# OpenBook_v29.net
KiCad netlist of a schematic drawn in EAGLE
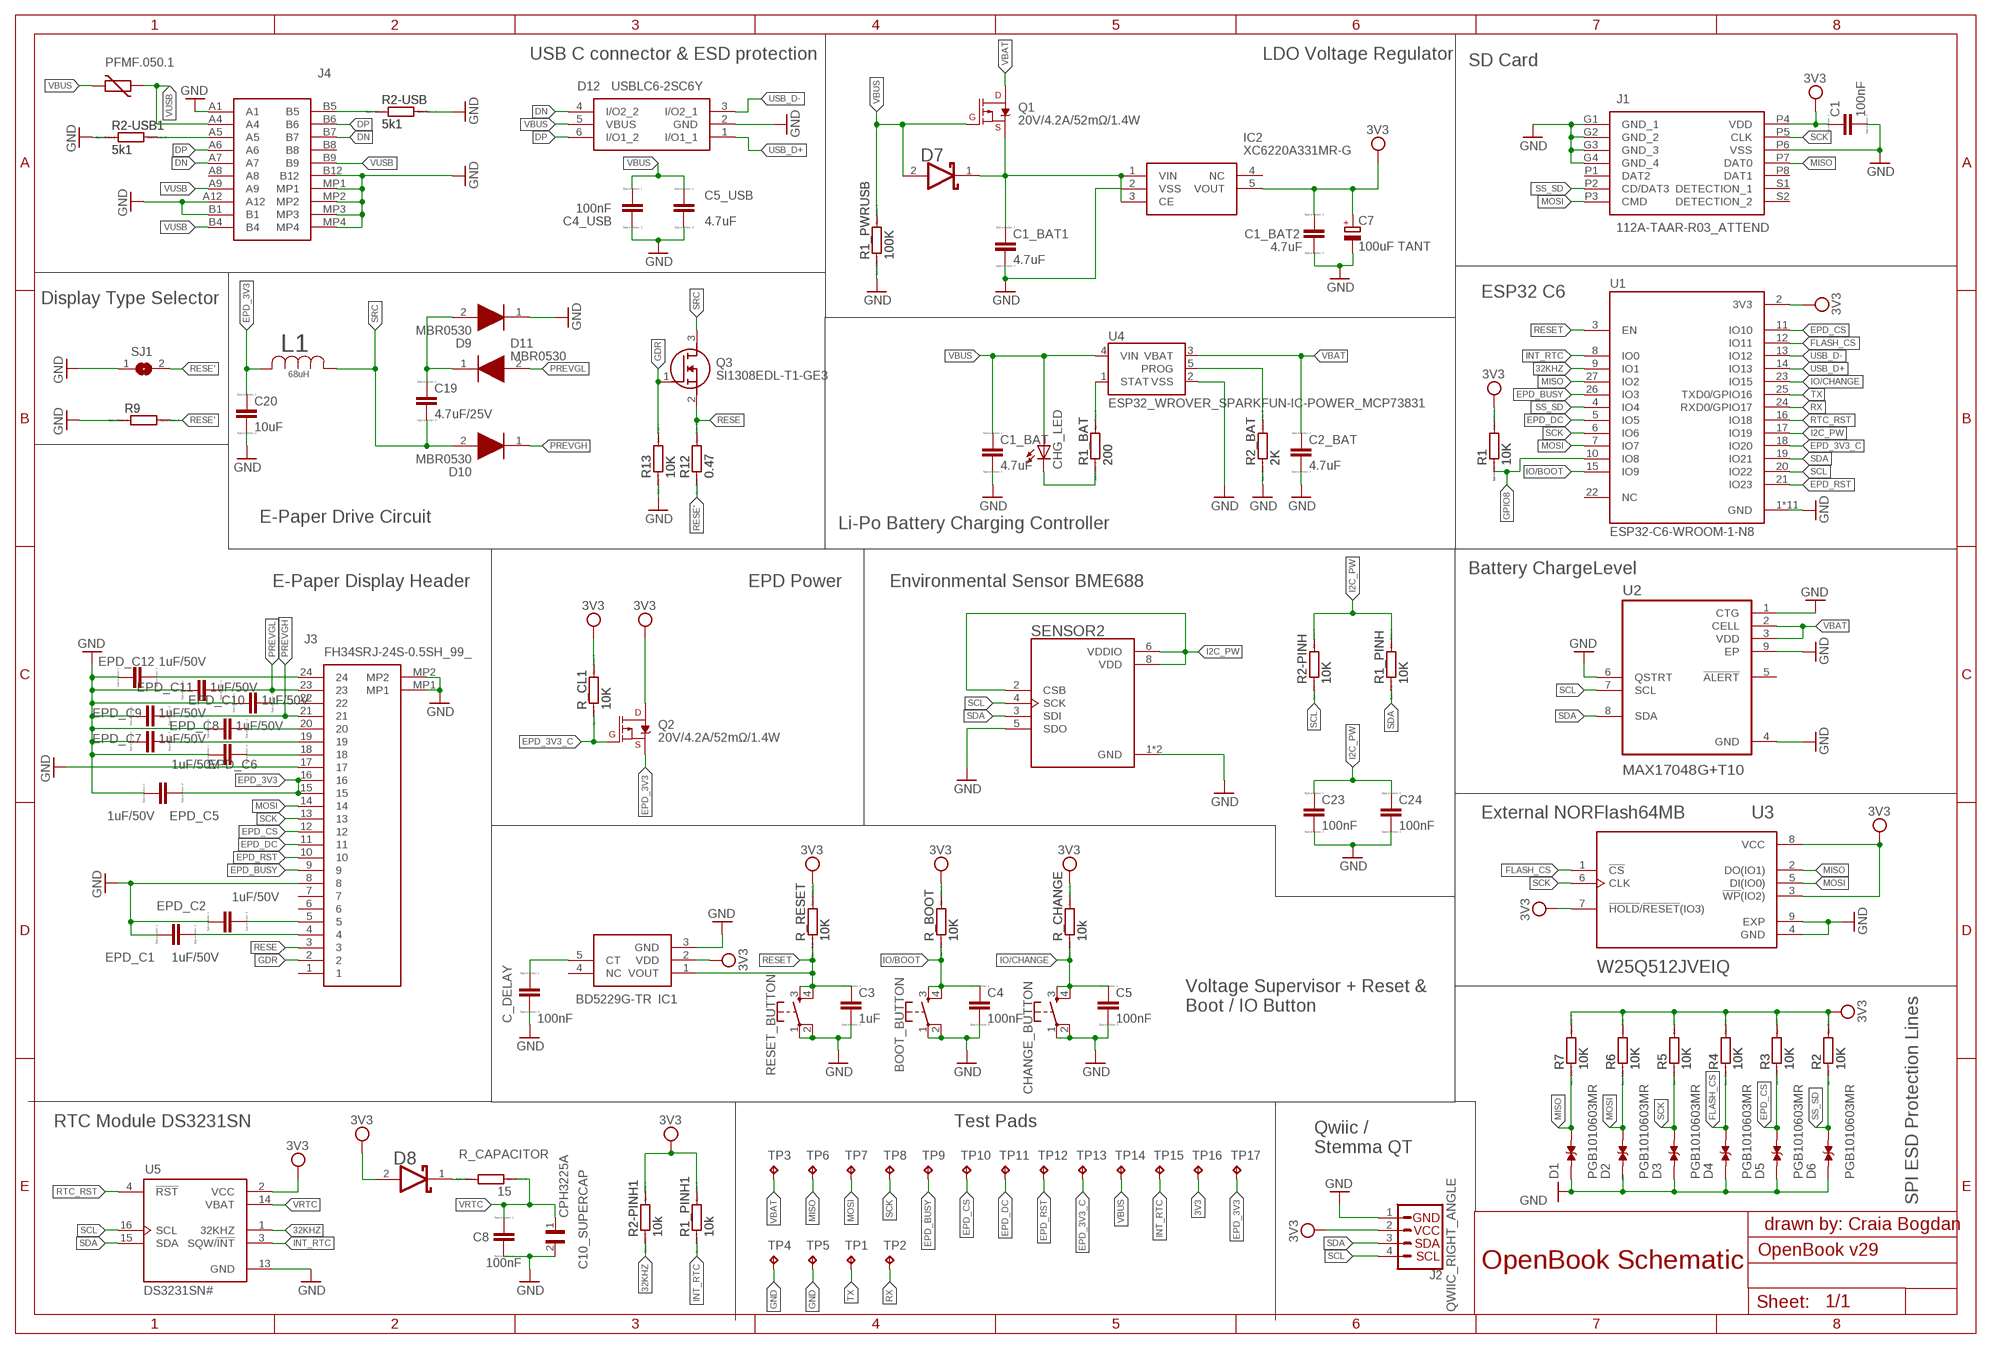
[diagram p0: schematic, sheet 1]

(export (version "E")
  (design (tool "Eeschema 10.0.6"))
  (components
    (comp (ref "BOOT_BUTTON")
      (value "BUTTON_CUSYOMV1")
      (footprint "eagle-import:MYBUTTON")
      (libsource (lib "eagle-import") (part "BUTTON_CUSYOMV1"))
    )
    (comp (ref "C1")
      (value "100nF")
      (footprint "eagle-import:EAGLE-LTSPICE_C0402")
      (libsource (lib "eagle-import") (part "EAGLE-LTSPICE_CC0402"))
    )
    (comp (ref "C1_BAT")
      (value "4.7uF")
      (footprint "eagle-import:EAGLE-LTSPICE_C0402")
      (libsource (lib "eagle-import") (part "EAGLE-LTSPICE_CC0402"))
    )
    (comp (ref "C1_BAT1")
      (value "4.7uF")
      (footprint "eagle-import:EAGLE-LTSPICE_C0402")
      (libsource (lib "eagle-import") (part "EAGLE-LTSPICE_CC0402"))
    )
    (comp (ref "C1_BAT2")
      (value "4.7uF")
      (footprint "eagle-import:EAGLE-LTSPICE_C0402")
      (libsource (lib "eagle-import") (part "EAGLE-LTSPICE_CC0402"))
    )
    (comp (ref "C2_BAT")
      (value "4.7uF")
      (footprint "eagle-import:EAGLE-LTSPICE_C0402")
      (libsource (lib "eagle-import") (part "EAGLE-LTSPICE_CC0402"))
    )
    (comp (ref "C3")
      (value "1uF")
      (footprint "eagle-import:EAGLE-LTSPICE_C0402")
      (libsource (lib "eagle-import") (part "EAGLE-LTSPICE_CC0402"))
    )
    (comp (ref "C4")
      (value "100nF")
      (footprint "eagle-import:EAGLE-LTSPICE_C0402")
      (libsource (lib "eagle-import") (part "EAGLE-LTSPICE_CC0402"))
    )
    (comp (ref "C4_USB")
      (value "100nF")
      (footprint "eagle-import:EAGLE-LTSPICE_C0402")
      (libsource (lib "eagle-import") (part "EAGLE-LTSPICE_CC0402"))
    )
    (comp (ref "C5")
      (value "100nF")
      (footprint "eagle-import:EAGLE-LTSPICE_C0402")
      (libsource (lib "eagle-import") (part "EAGLE-LTSPICE_CC0402"))
    )
    (comp (ref "C5_USB")
      (value "4.7uF")
      (footprint "eagle-import:EAGLE-LTSPICE_C0402")
      (libsource (lib "eagle-import") (part "EAGLE-LTSPICE_CC0402"))
    )
    (comp (ref "C7")
      (value "100uF TANT")
      (footprint "eagle-import:RCL_CT3528")
      (libsource (lib "eagle-import") (part "RCL_CPOL-EUCT3528"))
    )
    (comp (ref "C8")
      (value "100nF")
      (footprint "eagle-import:EAGLE-LTSPICE_C0402")
      (libsource (lib "eagle-import") (part "EAGLE-LTSPICE_CC0402"))
    )
    (comp (ref "C10_SUPERCAP")
      (value "CPH3225A")
      (footprint "eagle-import:CAPCP3225X100N")
      (fields (field (name "MF") "Seiko Instruments"))
      (libsource (lib "eagle-import") (part "CPH3225A"))
    )
    (comp (ref "C19")
      (value "4.7uF/25V")
      (footprint "eagle-import:EAGLE-LTSPICE_C0402")
      (libsource (lib "eagle-import") (part "EAGLE-LTSPICE_CC0402"))
    )
    (comp (ref "C20")
      (value "10uF")
      (footprint "eagle-import:EAGLE-LTSPICE_C0402")
      (libsource (lib "eagle-import") (part "EAGLE-LTSPICE_CC0402"))
    )
    (comp (ref "C23")
      (value "100nF")
      (footprint "eagle-import:EAGLE-LTSPICE_C0402")
      (libsource (lib "eagle-import") (part "EAGLE-LTSPICE_CC0402"))
    )
    (comp (ref "C24")
      (value "100nF")
      (footprint "eagle-import:EAGLE-LTSPICE_C0402")
      (libsource (lib "eagle-import") (part "EAGLE-LTSPICE_CC0402"))
    )
    (comp (ref "CHANGE_BUTTON")
      (value "BUTTON_CUSYOMV1")
      (footprint "eagle-import:MYBUTTON")
      (libsource (lib "eagle-import") (part "BUTTON_CUSYOMV1"))
    )
    (comp (ref "CHG_LED")
      (value "ADAFRUIT_LEDCHIP-LED0603")
      (footprint "eagle-import:ADAFRUIT_CHIP-LED0603")
      (libsource (lib "eagle-import") (part "ADAFRUIT_LEDCHIP-LED0603"))
    )
    (comp (ref "C_DELAY")
      (value "100nF")
      (footprint "eagle-import:EAGLE-LTSPICE_C0402")
      (libsource (lib "eagle-import") (part "EAGLE-LTSPICE_CC0402"))
    )
    (comp (ref "D1")
      (value "PGB1010603MR")
      (footprint "eagle-import:DIOC1608X36N")
      (fields (field (name "MF") "Littelfuse Inc."))
      (libsource (lib "eagle-import") (part "PGB1010603MR"))
    )
    (comp (ref "D2")
      (value "PGB1010603MR")
      (footprint "eagle-import:DIOC1608X36N")
      (fields (field (name "MF") "Littelfuse Inc."))
      (libsource (lib "eagle-import") (part "PGB1010603MR"))
    )
    (comp (ref "D3")
      (value "PGB1010603MR")
      (footprint "eagle-import:DIOC1608X36N")
      (fields (field (name "MF") "Littelfuse Inc."))
      (libsource (lib "eagle-import") (part "PGB1010603MR"))
    )
    (comp (ref "D4")
      (value "PGB1010603MR")
      (footprint "eagle-import:DIOC1608X36N")
      (fields (field (name "MF") "Littelfuse Inc."))
      (libsource (lib "eagle-import") (part "PGB1010603MR"))
    )
    (comp (ref "D5")
      (value "PGB1010603MR")
      (footprint "eagle-import:DIOC1608X36N")
      (fields (field (name "MF") "Littelfuse Inc."))
      (libsource (lib "eagle-import") (part "PGB1010603MR"))
    )
    (comp (ref "D6")
      (value "PGB1010603MR")
      (footprint "eagle-import:DIOC1608X36N")
      (fields (field (name "MF") "Littelfuse Inc."))
      (libsource (lib "eagle-import") (part "PGB1010603MR"))
    )
    (comp (ref "D7")
      (value "ESP32_WROVER_AVX---SD0805S020S1R0_AVX_SD0805S020S1R0_0_0AVX_SD0805S020S1R0_0_0")
      (footprint "eagle-import:ESP32_WROVER_AVX---SD0805S020S1R0_AVX_SD0805S020S1R0_0")
      (fields
        (field (name "DIGIKEY_PART_NUMBER") "478-7800-1-ND")
        (field (name "MF") "AVX")
        (field (name "MOUSER_PART_NUMBER") "581-SD0805S020S1R0")
      )
      (libsource (lib "eagle-import") (part "ESP32_WROVER_AVX---SD0805S020S1R0_AVX_SD0805S020S1R0_0_0AVX_SD0805S020S1R0_0_0"))
    )
    (comp (ref "D8")
      (value "ESP32_WROVER_AVX---SD0805S020S1R0_AVX_SD0805S020S1R0_0_0AVX_SD0805S020S1R0_0_0")
      (footprint "eagle-import:ESP32_WROVER_AVX---SD0805S020S1R0_AVX_SD0805S020S1R0_0")
      (fields
        (field (name "DIGIKEY_PART_NUMBER") "478-7800-1-ND")
        (field (name "MF") "AVX")
        (field (name "MOUSER_PART_NUMBER") "581-SD0805S020S1R0")
      )
      (libsource (lib "eagle-import") (part "ESP32_WROVER_AVX---SD0805S020S1R0_AVX_SD0805S020S1R0_0_0AVX_SD0805S020S1R0_0_0"))
    )
    (comp (ref "D9")
      (value "MBR0530")
      (footprint "eagle-import:SOD3716X135N")
      (fields (field (name "MF") "ON Semiconductor"))
      (libsource (lib "eagle-import") (part "MBR0530"))
    )
    (comp (ref "D10")
      (value "MBR0530")
      (footprint "eagle-import:SOD3716X135N")
      (fields (field (name "MF") "ON Semiconductor"))
      (libsource (lib "eagle-import") (part "MBR0530"))
    )
    (comp (ref "D11")
      (value "MBR0530")
      (footprint "eagle-import:SOD3716X135N")
      (fields (field (name "MF") "ON Semiconductor"))
      (libsource (lib "eagle-import") (part "MBR0530"))
    )
    (comp (ref "D12")
      (value "USBLC6-2SC6Y")
      (footprint "eagle-import:SOT95P280X145-6N")
      (fields (field (name "MF") "STMicroelectronics"))
      (libsource (lib "eagle-import") (part "USBLC6-2SC6Y"))
    )
    (comp (ref "EPD_C1")
      (value "1uF/50V")
      (footprint "eagle-import:EAGLE-LTSPICE_C0402")
      (libsource (lib "eagle-import") (part "EAGLE-LTSPICE_CC0402"))
    )
    (comp (ref "EPD_C2")
      (value "1uF/50V")
      (footprint "eagle-import:EAGLE-LTSPICE_C0402")
      (libsource (lib "eagle-import") (part "EAGLE-LTSPICE_CC0402"))
    )
    (comp (ref "EPD_C5")
      (value "1uF/50V")
      (footprint "eagle-import:EAGLE-LTSPICE_C0402")
      (libsource (lib "eagle-import") (part "EAGLE-LTSPICE_CC0402"))
    )
    (comp (ref "EPD_C6")
      (value "1uF/50V")
      (footprint "eagle-import:EAGLE-LTSPICE_C0402")
      (libsource (lib "eagle-import") (part "EAGLE-LTSPICE_CC0402"))
    )
    (comp (ref "EPD_C7")
      (value "1uF/50V")
      (footprint "eagle-import:EAGLE-LTSPICE_C0402")
      (libsource (lib "eagle-import") (part "EAGLE-LTSPICE_CC0402"))
    )
    (comp (ref "EPD_C8")
      (value "1uF/50V")
      (footprint "eagle-import:EAGLE-LTSPICE_C0402")
      (libsource (lib "eagle-import") (part "EAGLE-LTSPICE_CC0402"))
    )
    (comp (ref "EPD_C9")
      (value "1uF/50V")
      (footprint "eagle-import:EAGLE-LTSPICE_C0402")
      (libsource (lib "eagle-import") (part "EAGLE-LTSPICE_CC0402"))
    )
    (comp (ref "EPD_C10")
      (value "1uF/50V")
      (footprint "eagle-import:EAGLE-LTSPICE_C0402")
      (libsource (lib "eagle-import") (part "EAGLE-LTSPICE_CC0402"))
    )
    (comp (ref "EPD_C11")
      (value "1uF/50V")
      (footprint "eagle-import:EAGLE-LTSPICE_C0402")
      (libsource (lib "eagle-import") (part "EAGLE-LTSPICE_CC0402"))
    )
    (comp (ref "EPD_C12")
      (value "1uF/50V")
      (footprint "eagle-import:EAGLE-LTSPICE_C0402")
      (libsource (lib "eagle-import") (part "EAGLE-LTSPICE_CC0402"))
    )
    (comp (ref "IC1")
      (value "BD5229G-TR")
      (footprint "eagle-import:SOT95P280X125-5N")
      (fields (field (name "MOUSER_PART_NUMBER") "755-BD5229G-TR"))
      (libsource (lib "eagle-import") (part "BD5229G-TR"))
    )
    (comp (ref "IC2")
      (value "XC6220A331MR-G")
      (footprint "eagle-import:SOT95P280X120-5N")
      (fields (field (name "MOUSER_PART_NUMBER") "865-XC6220A331MR-G"))
      (libsource (lib "eagle-import") (part "XC6220A331MR-G"))
    )
    (comp (ref "J1")
      (value "112A-TAAR-R03_ATTEND")
      (footprint "eagle-import:112ATAARR03ATTEND")
      (fields (field (name "MANUFACTURER_PART_NUMBER") "112A-TAAR-R03 ATTEND"))
      (libsource (lib "eagle-import") (part "112A-TAAR-R03_ATTEND"))
    )
    (comp (ref "J2")
      (value "QWIIC_RIGHT_ANGLE")
      (footprint "eagle-import:JST04_1MM_RA")
      (libsource (lib "eagle-import") (part "QWIIC_CONNECTORJS-1MM"))
    )
    (comp (ref "J3")
      (value "FH34SRJ-24S-0.5SH_99_")
      (footprint "eagle-import:FH34SRJ24S05SH99")
      (fields
        (field (name "MANUFACTURER_PART_NUMBER") "FH34SRJ-24S-0.5SH(99)")
        (field (name "MOUSER_PART_NUMBER") "798-FH34SRJ24S05SH99")
      )
      (libsource (lib "eagle-import") (part "FH34SRJ-24S-0.5SH_99_"))
    )
    (comp (ref "J4")
      (value "SAMACSYS_PARTS_USB4110-GF-A")
      (footprint "eagle-import:SAMACSYS_PARTS_USB4110GFA")
      (fields
        (field (name "MANUFACTURER_PART_NUMBER") "USB4110-GF-A")
        (field (name "MOUSER_PART_NUMBER") "640-USB4110-GF-A")
      )
      (libsource (lib "eagle-import") (part "SAMACSYS_PARTS_USB4110-GF-A"))
    )
    (comp (ref "L1")
      (value "68uH")
      (footprint "eagle-import:IND_4828-WE-TPC_WRE")
      (fields
        (field (name "MANUFACTURER_PART_NUMBER") "744043680")
        (field (name "COPYRIGHT") "Copyright (C) 2024 Ultra Librarian. All rights reserved.")
      )
      (libsource (lib "eagle-import") (part "744043680IND_4828-WE-TPC_WRE"))
    )
    (comp (ref "PFMF.050.1")
      (value "ESP32C6_VARISTORCN1812")
      (footprint "eagle-import:ESP32C6_VARISTOR_CT_CN1812")
      (libsource (lib "eagle-import") (part "ESP32C6_VARISTORCN1812"))
    )
    (comp (ref "Q1")
      (value "20V/4.2A/52mΩ/1.4W")
      (footprint "eagle-import:ESP32_WROVER_SPARKFUN-DISCRETESEMI_SOT23-3")
      (libsource (lib "eagle-import") (part "ESP32_WROVER_SPARKFUN-DISCRETESEMI_MOSFET_PCH-DMG2305UX-7"))
    )
    (comp (ref "Q2")
      (value "20V/4.2A/52mΩ/1.4W")
      (footprint "eagle-import:ESP32_WROVER_SPARKFUN-DISCRETESEMI_SOT23-3")
      (libsource (lib "eagle-import") (part "ESP32_WROVER_SPARKFUN-DISCRETESEMI_MOSFET_PCH-DMG2305UX-7"))
    )
    (comp (ref "Q3")
      (value "SI1308EDL-T1-GE3")
      (footprint "eagle-import:SOT65P210X110-3N")
      (fields (field (name "MF") "Vishay Siliconix"))
      (libsource (lib "eagle-import") (part "SI1308EDL-T1-GE3"))
    )
    (comp (ref "R1")
      (value "10K")
      (footprint "eagle-import:ESP32_WROVER_EAGLE-LTSPICE_R0402")
      (libsource (lib "eagle-import") (part "ESP32_WROVER_EAGLE-LTSPICE_RR0402"))
    )
    (comp (ref "R1_BAT")
      (value "200")
      (footprint "eagle-import:ESP32_WROVER_EAGLE-LTSPICE_R0402")
      (libsource (lib "eagle-import") (part "ESP32_WROVER_EAGLE-LTSPICE_RR0402"))
    )
    (comp (ref "R1_PINH")
      (value "10K")
      (footprint "eagle-import:ESP32_WROVER_EAGLE-LTSPICE_R0402")
      (libsource (lib "eagle-import") (part "ESP32_WROVER_EAGLE-LTSPICE_RR0402"))
    )
    (comp (ref "R1_PINH1")
      (value "10k")
      (footprint "eagle-import:ESP32_WROVER_EAGLE-LTSPICE_R0402")
      (libsource (lib "eagle-import") (part "ESP32_WROVER_EAGLE-LTSPICE_RR0402"))
    )
    (comp (ref "R1_PWRUSB")
      (value "100K")
      (footprint "eagle-import:ESP32_WROVER_EAGLE-LTSPICE_R0402")
      (libsource (lib "eagle-import") (part "ESP32_WROVER_EAGLE-LTSPICE_RR0402"))
    )
    (comp (ref "R2")
      (value "10K")
      (footprint "eagle-import:ESP32_WROVER_EAGLE-LTSPICE_R0402")
      (libsource (lib "eagle-import") (part "ESP32_WROVER_EAGLE-LTSPICE_RR0402"))
    )
    (comp (ref "R2-PINH")
      (value "10K")
      (footprint "eagle-import:ESP32_WROVER_EAGLE-LTSPICE_R0402")
      (libsource (lib "eagle-import") (part "ESP32_WROVER_EAGLE-LTSPICE_RR0402"))
    )
    (comp (ref "R2-PINH1")
      (value "10k")
      (footprint "eagle-import:ESP32_WROVER_EAGLE-LTSPICE_R0402")
      (libsource (lib "eagle-import") (part "ESP32_WROVER_EAGLE-LTSPICE_RR0402"))
    )
    (comp (ref "R2-USB")
      (value "5k1")
      (footprint "eagle-import:ESP32_WROVER_EAGLE-LTSPICE_R0402")
      (libsource (lib "eagle-import") (part "ESP32_WROVER_EAGLE-LTSPICE_RR0402"))
    )
    (comp (ref "R2-USB1")
      (value "5k1")
      (footprint "eagle-import:ESP32_WROVER_EAGLE-LTSPICE_R0402")
      (libsource (lib "eagle-import") (part "ESP32_WROVER_EAGLE-LTSPICE_RR0402"))
    )
    (comp (ref "R2_BAT")
      (value "2K")
      (footprint "eagle-import:ESP32_WROVER_EAGLE-LTSPICE_R0402")
      (libsource (lib "eagle-import") (part "ESP32_WROVER_EAGLE-LTSPICE_RR0402"))
    )
    (comp (ref "R3")
      (value "10K")
      (footprint "eagle-import:ESP32_WROVER_EAGLE-LTSPICE_R0402")
      (libsource (lib "eagle-import") (part "ESP32_WROVER_EAGLE-LTSPICE_RR0402"))
    )
    (comp (ref "R4")
      (value "10K")
      (footprint "eagle-import:ESP32_WROVER_EAGLE-LTSPICE_R0402")
      (libsource (lib "eagle-import") (part "ESP32_WROVER_EAGLE-LTSPICE_RR0402"))
    )
    (comp (ref "R5")
      (value "10K")
      (footprint "eagle-import:ESP32_WROVER_EAGLE-LTSPICE_R0402")
      (libsource (lib "eagle-import") (part "ESP32_WROVER_EAGLE-LTSPICE_RR0402"))
    )
    (comp (ref "R6")
      (value "10K")
      (footprint "eagle-import:ESP32_WROVER_EAGLE-LTSPICE_R0402")
      (libsource (lib "eagle-import") (part "ESP32_WROVER_EAGLE-LTSPICE_RR0402"))
    )
    (comp (ref "R7")
      (value "10K")
      (footprint "eagle-import:ESP32_WROVER_EAGLE-LTSPICE_R0402")
      (libsource (lib "eagle-import") (part "ESP32_WROVER_EAGLE-LTSPICE_RR0402"))
    )
    (comp (ref "R9")
      (value "ESP32_WROVER_EAGLE-LTSPICE_RR0402")
      (footprint "eagle-import:ESP32_WROVER_EAGLE-LTSPICE_R0402")
      (libsource (lib "eagle-import") (part "ESP32_WROVER_EAGLE-LTSPICE_RR0402"))
    )
    (comp (ref "R12")
      (value "0.47")
      (footprint "eagle-import:ESP32_WROVER_EAGLE-LTSPICE_R0402")
      (libsource (lib "eagle-import") (part "ESP32_WROVER_EAGLE-LTSPICE_RR0402"))
    )
    (comp (ref "R13")
      (value "10K")
      (footprint "eagle-import:ESP32_WROVER_EAGLE-LTSPICE_R0402")
      (libsource (lib "eagle-import") (part "ESP32_WROVER_EAGLE-LTSPICE_RR0402"))
    )
    (comp (ref "RESET_BUTTON")
      (value "BUTTON_CUSYOMV1")
      (footprint "eagle-import:MYBUTTON")
      (libsource (lib "eagle-import") (part "BUTTON_CUSYOMV1"))
    )
    (comp (ref "R_BOOT")
      (value "10K")
      (footprint "eagle-import:ESP32_WROVER_EAGLE-LTSPICE_R0402")
      (libsource (lib "eagle-import") (part "ESP32_WROVER_EAGLE-LTSPICE_RR0402"))
    )
    (comp (ref "R_CAPACITOR")
      (value "15")
      (footprint "eagle-import:ESP32_WROVER_EAGLE-LTSPICE_R0402")
      (libsource (lib "eagle-import") (part "ESP32_WROVER_EAGLE-LTSPICE_RR0402"))
    )
    (comp (ref "R_CHANGE")
      (value "10k")
      (footprint "eagle-import:ESP32_WROVER_EAGLE-LTSPICE_R0402")
      (libsource (lib "eagle-import") (part "ESP32_WROVER_EAGLE-LTSPICE_RR0402"))
    )
    (comp (ref "R_CL1")
      (value "10K")
      (footprint "eagle-import:ESP32_WROVER_EAGLE-LTSPICE_R0402")
      (libsource (lib "eagle-import") (part "ESP32_WROVER_EAGLE-LTSPICE_RR0402"))
    )
    (comp (ref "R_RESET")
      (value "10K")
      (footprint "eagle-import:ESP32_WROVER_EAGLE-LTSPICE_R0402")
      (libsource (lib "eagle-import") (part "ESP32_WROVER_EAGLE-LTSPICE_RR0402"))
    )
    (comp (ref "SENSOR2")
      (value "ESP32_WROVER_BME680_BME680")
      (footprint "eagle-import:ESP32_WROVER_BME680_PSON80P300X300X100-8N")
      (fields (field (name "MF") "Bosch Sensortec") (field (name "MP") "BME680"))
      (libsource (lib "eagle-import") (part "ESP32_WROVER_BME680_BME680"))
    )
    (comp (ref "SJ1") (value "SJ") (footprint "eagle-import:SJ") (libsource (lib "eagle-import") (part "SJ")))
    (comp (ref "TP1")
      (value "TPTP20R")
      (footprint "eagle-import:TP20R")
      (libsource (lib "eagle-import") (part "TPTP20R"))
    )
    (comp (ref "TP2")
      (value "TPTP20R")
      (footprint "eagle-import:TP20R")
      (libsource (lib "eagle-import") (part "TPTP20R"))
    )
    (comp (ref "TP3")
      (value "TPTP20R")
      (footprint "eagle-import:TP20R")
      (libsource (lib "eagle-import") (part "TPTP20R"))
    )
    (comp (ref "TP4")
      (value "TPTP20R")
      (footprint "eagle-import:TP20R")
      (libsource (lib "eagle-import") (part "TPTP20R"))
    )
    (comp (ref "TP5")
      (value "TPTP20R")
      (footprint "eagle-import:TP20R")
      (libsource (lib "eagle-import") (part "TPTP20R"))
    )
    (comp (ref "TP6")
      (value "TPTP20R")
      (footprint "eagle-import:TP20R")
      (libsource (lib "eagle-import") (part "TPTP20R"))
    )
    (comp (ref "TP7")
      (value "TPTP20R")
      (footprint "eagle-import:TP20R")
      (libsource (lib "eagle-import") (part "TPTP20R"))
    )
    (comp (ref "TP8")
      (value "TPTP20R")
      (footprint "eagle-import:TP20R")
      (libsource (lib "eagle-import") (part "TPTP20R"))
    )
    (comp (ref "TP9")
      (value "TPTP20R")
      (footprint "eagle-import:TP20R")
      (libsource (lib "eagle-import") (part "TPTP20R"))
    )
    (comp (ref "TP10")
      (value "TPTP20R")
      (footprint "eagle-import:TP20R")
      (libsource (lib "eagle-import") (part "TPTP20R"))
    )
    (comp (ref "TP11")
      (value "TPTP20R")
      (footprint "eagle-import:TP20R")
      (libsource (lib "eagle-import") (part "TPTP20R"))
    )
    (comp (ref "TP12")
      (value "TPTP20R")
      (footprint "eagle-import:TP20R")
      (libsource (lib "eagle-import") (part "TPTP20R"))
    )
    (comp (ref "TP13")
      (value "TPTP20R")
      (footprint "eagle-import:TP20R")
      (libsource (lib "eagle-import") (part "TPTP20R"))
    )
    (comp (ref "TP14")
      (value "TPTP20R")
      (footprint "eagle-import:TP20R")
      (libsource (lib "eagle-import") (part "TPTP20R"))
    )
    (comp (ref "TP15")
      (value "TPTP20R")
      (footprint "eagle-import:TP20R")
      (libsource (lib "eagle-import") (part "TPTP20R"))
    )
    (comp (ref "TP16")
      (value "TPTP20R")
      (footprint "eagle-import:TP20R")
      (libsource (lib "eagle-import") (part "TPTP20R"))
    )
    (comp (ref "TP17")
      (value "TPTP20R")
      (footprint "eagle-import:TP20R")
      (libsource (lib "eagle-import") (part "TPTP20R"))
    )
    (comp (ref "U1")
      (value "ESP32-C6-WROOM-1-N8")
      (footprint "eagle-import:XCVR_ESP32-C6-WROOM-1-N8")
      (fields (field (name "MF") "Espressif Systems"))
      (libsource (lib "eagle-import") (part "ESP32-C6-WROOM-1-N8"))
    )
    (comp (ref "U2")
      (value "MAX17048G+T10")
      (footprint "eagle-import:SON50P200X200X80-9N")
      (fields (field (name "MF") "Analog Devices"))
      (libsource (lib "eagle-import") (part "MAX17048G+T10"))
    )
    (comp (ref "U3")
      (value "W25Q512JVEIQ")
      (footprint "eagle-import:SON127P600X800X80-9N")
      (fields (field (name "MF") "Winbond Electronics"))
      (libsource (lib "eagle-import") (part "W25Q512JVEIQ"))
    )
    (comp (ref "U4")
      (value "ESP32_WROVER_SPARKFUN-IC-POWER_MCP73831")
      (footprint "eagle-import:ESP32_WROVER_SPARKFUN-IC-POWER_SOT23-5")
      (libsource (lib "eagle-import") (part "ESP32_WROVER_SPARKFUN-IC-POWER_MCP73831"))
    )
    (comp (ref "U5")
      (value "DS3231SN#")
      (footprint "eagle-import:SOIC127P1032X265-16N")
      (fields (field (name "MF") "Analog Devices"))
      (libsource (lib "eagle-import") (part "DS3231SN#"))
    )
  )
  (nets
    (net (code "1") (name "3V3") (class "Default")
      (node (ref "C1") (pin "1") (pinfunction "1_1") (pintype "passive"))
      (node (ref "C1_BAT2") (pin "1") (pinfunction "1_1") (pintype "passive"))
      (node (ref "C7") (pin "+") (pinfunction "+_+") (pintype "passive"))
      (node (ref "D8") (pin "2") (pinfunction "ANODE_2") (pintype "bidirectional"))
      (node (ref "IC1") (pin "2") (pinfunction "VDD_2") (pintype "bidirectional"))
      (node (ref "IC2") (pin "5") (pinfunction "VOUT_5") (pintype "bidirectional"))
      (node (ref "J1") (pin "P4") (pinfunction "VDD_P4") (pintype "bidirectional"))
      (node (ref "J2") (pin "2") (pinfunction "2_2") (pintype "power_in"))
      (node (ref "Q2") (pin "3") (pinfunction "D_3") (pintype "bidirectional"))
      (node (ref "R1") (pin "2") (pinfunction "2_2") (pintype "passive"))
      (node (ref "R1_PINH1") (pin "2") (pinfunction "2_2") (pintype "passive"))
      (node (ref "R2") (pin "2") (pinfunction "2_2") (pintype "passive"))
      (node (ref "R2-PINH1") (pin "2") (pinfunction "2_2") (pintype "passive"))
      (node (ref "R3") (pin "2") (pinfunction "2_2") (pintype "passive"))
      (node (ref "R4") (pin "2") (pinfunction "2_2") (pintype "passive"))
      (node (ref "R5") (pin "2") (pinfunction "2_2") (pintype "passive"))
      (node (ref "R6") (pin "2") (pinfunction "2_2") (pintype "passive"))
      (node (ref "R7") (pin "2") (pinfunction "2_2") (pintype "passive"))
      (node (ref "R_BOOT") (pin "2") (pinfunction "2_2") (pintype "passive"))
      (node (ref "R_CHANGE") (pin "2") (pinfunction "2_2") (pintype "passive"))
      (node (ref "R_CL1") (pin "2") (pinfunction "2_2") (pintype "passive"))
      (node (ref "R_RESET") (pin "2") (pinfunction "2_2") (pintype "passive"))
      (node (ref "TP16") (pin "TP") (pinfunction "TP_TP") (pintype "input"))
      (node (ref "U1") (pin "2") (pinfunction "3V3_2") (pintype "power_in"))
      (node (ref "U3") (pin "3") (pinfunction "~{WP}(IO2)_3") (pintype "bidirectional"))
      (node (ref "U3") (pin "7") (pinfunction "~{HOLD}/~{RESET}(IO3)_7") (pintype "bidirectional"))
      (node (ref "U3") (pin "8") (pinfunction "VCC_8") (pintype "power_in"))
      (node (ref "U5") (pin "2") (pinfunction "VCC_2") (pintype "power_in"))
    )
    (net (code "2") (name "32KHZ") (class "Default")
      (node (ref "R2-PINH1") (pin "1") (pinfunction "1_1") (pintype "passive"))
      (node (ref "U1") (pin "9") (pinfunction "IO1_9") (pintype "bidirectional"))
      (node (ref "U5") (pin "1") (pinfunction "32KHZ_1") (pintype "output"))
    )
    (net (code "3") (name "DN") (class "Default")
      (node (ref "D12") (pin "4") (pinfunction "I/O2_2_4") (pintype "bidirectional"))
      (node (ref "J4") (pin "A7") (pinfunction "A7_A7") (pintype "bidirectional"))
      (node (ref "J4") (pin "B7") (pinfunction "B7_B7") (pintype "bidirectional"))
    )
    (net (code "4") (name "DP") (class "Default")
      (node (ref "D12") (pin "6") (pinfunction "I/O1_2_6") (pintype "bidirectional"))
      (node (ref "J4") (pin "A6") (pinfunction "A6_A6") (pintype "bidirectional"))
      (node (ref "J4") (pin "B6") (pinfunction "B6_B6") (pintype "bidirectional"))
    )
    (net (code "5") (name "EPD_3V3") (class "Default")
      (node (ref "C20") (pin "1") (pinfunction "1_1") (pintype "passive"))
      (node (ref "EPD_C5") (pin "2") (pinfunction "2_2") (pintype "passive"))
      (node (ref "J3") (pin "15") (pinfunction "15_15") (pintype "bidirectional"))
      (node (ref "J3") (pin "16") (pinfunction "16_16") (pintype "bidirectional"))
      (node (ref "L1") (pin "2") (pinfunction "2_2") (pintype "passive"))
      (node (ref "Q2") (pin "2") (pinfunction "S_2") (pintype "bidirectional"))
      (node (ref "TP17") (pin "TP") (pinfunction "TP_TP") (pintype "input"))
    )
    (net (code "6") (name "EPD_3V3_C") (class "Default")
      (node (ref "Q2") (pin "1") (pinfunction "G_1") (pintype "bidirectional"))
      (node (ref "R_CL1") (pin "1") (pinfunction "1_1") (pintype "passive"))
      (node (ref "TP13") (pin "TP") (pinfunction "TP_TP") (pintype "input"))
      (node (ref "U1") (pin "18") (pinfunction "IO20_18") (pintype "bidirectional"))
    )
    (net (code "7") (name "EPD_BUSY") (class "Default")
      (node (ref "J3") (pin "9") (pinfunction "9_9") (pintype "bidirectional"))
      (node (ref "TP9") (pin "TP") (pinfunction "TP_TP") (pintype "input"))
      (node (ref "U1") (pin "26") (pinfunction "IO3_26") (pintype "bidirectional"))
    )
    (net (code "8") (name "EPD_CS") (class "Default")
      (node (ref "D5") (pin "2") (pinfunction "2_2") (pintype "passive"))
      (node (ref "J3") (pin "12") (pinfunction "12_12") (pintype "bidirectional"))
      (node (ref "R3") (pin "1") (pinfunction "1_1") (pintype "passive"))
      (node (ref "TP10") (pin "TP") (pinfunction "TP_TP") (pintype "input"))
      (node (ref "U1") (pin "11") (pinfunction "IO10_11") (pintype "bidirectional"))
    )
    (net (code "9") (name "EPD_DC") (class "Default")
      (node (ref "J3") (pin "11") (pinfunction "11_11") (pintype "bidirectional"))
      (node (ref "TP11") (pin "TP") (pinfunction "TP_TP") (pintype "input"))
      (node (ref "U1") (pin "5") (pinfunction "IO5_5") (pintype "bidirectional"))
    )
    (net (code "10") (name "EPD_RST") (class "Default")
      (node (ref "J3") (pin "10") (pinfunction "10_10") (pintype "bidirectional"))
      (node (ref "TP12") (pin "TP") (pinfunction "TP_TP") (pintype "input"))
      (node (ref "U1") (pin "21") (pinfunction "IO23_21") (pintype "bidirectional"))
    )
    (net (code "11") (name "FLASH_CS") (class "Default")
      (node (ref "D4") (pin "2") (pinfunction "2_2") (pintype "passive"))
      (node (ref "R4") (pin "1") (pinfunction "1_1") (pintype "passive"))
      (node (ref "U1") (pin "12") (pinfunction "IO11_12") (pintype "bidirectional"))
      (node (ref "U3") (pin "1") (pinfunction "~{CS}_1") (pintype "input"))
    )
    (net (code "12") (name "GDR") (class "Default")
      (node (ref "J3") (pin "2") (pinfunction "2_2") (pintype "bidirectional"))
      (node (ref "Q3") (pin "1") (pinfunction "G_1") (pintype "bidirectional"))
      (node (ref "R13") (pin "2") (pinfunction "2_2") (pintype "passive"))
    )
    (net (code "13") (name "GND") (class "Default")
      (node (ref "BOOT_BUTTON") (pin "1") (pinfunction "1_1") (pintype "passive"))
      (node (ref "BOOT_BUTTON") (pin "2") (pinfunction "2_2") (pintype "passive"))
      (node (ref "C1") (pin "2") (pinfunction "2_2") (pintype "passive"))
      (node (ref "C10_SUPERCAP") (pin "2") (pinfunction "2_2") (pintype "passive"))
      (node (ref "C1_BAT") (pin "2") (pinfunction "2_2") (pintype "passive"))
      (node (ref "C1_BAT1") (pin "2") (pinfunction "2_2") (pintype "passive"))
      (node (ref "C1_BAT2") (pin "2") (pinfunction "2_2") (pintype "passive"))
      (node (ref "C20") (pin "2") (pinfunction "2_2") (pintype "passive"))
      (node (ref "C23") (pin "2") (pinfunction "2_2") (pintype "passive"))
      (node (ref "C24") (pin "2") (pinfunction "2_2") (pintype "passive"))
      (node (ref "C2_BAT") (pin "2") (pinfunction "2_2") (pintype "passive"))
      (node (ref "C3") (pin "2") (pinfunction "2_2") (pintype "passive"))
      (node (ref "C4") (pin "2") (pinfunction "2_2") (pintype "passive"))
      (node (ref "C4_USB") (pin "2") (pinfunction "2_2") (pintype "passive"))
      (node (ref "C5") (pin "2") (pinfunction "2_2") (pintype "passive"))
      (node (ref "C5_USB") (pin "2") (pinfunction "2_2") (pintype "passive"))
      (node (ref "C7") (pin "-") (pinfunction "-_-") (pintype "passive"))
      (node (ref "C8") (pin "2") (pinfunction "2_2") (pintype "passive"))
      (node (ref "CHANGE_BUTTON") (pin "1") (pinfunction "1_1") (pintype "passive"))
      (node (ref "CHANGE_BUTTON") (pin "2") (pinfunction "2_2") (pintype "passive"))
      (node (ref "C_DELAY") (pin "2") (pinfunction "2_2") (pintype "passive"))
      (node (ref "D1") (pin "1") (pinfunction "1_1") (pintype "passive"))
      (node (ref "D12") (pin "2") (pinfunction "GND_2") (pintype "bidirectional"))
      (node (ref "D2") (pin "1") (pinfunction "1_1") (pintype "passive"))
      (node (ref "D3") (pin "1") (pinfunction "1_1") (pintype "passive"))
      (node (ref "D4") (pin "1") (pinfunction "1_1") (pintype "passive"))
      (node (ref "D5") (pin "1") (pinfunction "1_1") (pintype "passive"))
      (node (ref "D6") (pin "1") (pinfunction "1_1") (pintype "passive"))
      (node (ref "D9") (pin "1") (pinfunction "K_1") (pintype "bidirectional"))
      (node (ref "EPD_C1") (pin "1") (pinfunction "1_1") (pintype "passive"))
      (node (ref "EPD_C10") (pin "1") (pinfunction "1_1") (pintype "passive"))
      (node (ref "EPD_C11") (pin "1") (pinfunction "1_1") (pintype "passive"))
      (node (ref "EPD_C12") (pin "1") (pinfunction "1_1") (pintype "passive"))
      (node (ref "EPD_C2") (pin "1") (pinfunction "1_1") (pintype "passive"))
      (node (ref "EPD_C5") (pin "1") (pinfunction "1_1") (pintype "passive"))
      (node (ref "EPD_C6") (pin "1") (pinfunction "1_1") (pintype "passive"))
      (node (ref "EPD_C7") (pin "1") (pinfunction "1_1") (pintype "passive"))
      (node (ref "EPD_C8") (pin "1") (pinfunction "1_1") (pintype "passive"))
      (node (ref "EPD_C9") (pin "1") (pinfunction "1_1") (pintype "passive"))
      (node (ref "IC1") (pin "3") (pinfunction "GND_3") (pintype "bidirectional"))
      (node (ref "IC2") (pin "2") (pinfunction "VSS_2") (pintype "bidirectional"))
      (node (ref "J1") (pin "G1") (pinfunction "GND_1_G1") (pintype "bidirectional"))
      (node (ref "J1") (pin "G2") (pinfunction "GND_2_G2") (pintype "bidirectional"))
      (node (ref "J1") (pin "G3") (pinfunction "GND_3_G3") (pintype "bidirectional"))
      (node (ref "J1") (pin "G4") (pinfunction "GND_4_G4") (pintype "bidirectional"))
      (node (ref "J1") (pin "P6") (pinfunction "VSS_P6") (pintype "bidirectional"))
      (node (ref "J2") (pin "1") (pinfunction "1_1") (pintype "power_in"))
      (node (ref "J3") (pin "17") (pinfunction "17_17") (pintype "bidirectional"))
      (node (ref "J3") (pin "8") (pinfunction "8_8") (pintype "bidirectional"))
      (node (ref "J3") (pin "MP1") (pinfunction "MP1_MP1") (pintype "bidirectional"))
      (node (ref "J3") (pin "MP2") (pinfunction "MP2_MP2") (pintype "bidirectional"))
      (node (ref "J4") (pin "A1") (pinfunction "A1_A1") (pintype "bidirectional"))
      (node (ref "J4") (pin "A12") (pinfunction "A12_A12") (pintype "bidirectional"))
      (node (ref "J4") (pin "B1") (pinfunction "B1_B1") (pintype "bidirectional"))
      (node (ref "J4") (pin "B12") (pinfunction "B12_B12") (pintype "bidirectional"))
      (node (ref "J4") (pin "MP1") (pinfunction "MP1_MP1") (pintype "bidirectional"))
      (node (ref "J4") (pin "MP2") (pinfunction "MP2_MP2") (pintype "bidirectional"))
      (node (ref "J4") (pin "MP3") (pinfunction "MP3_MP3") (pintype "bidirectional"))
      (node (ref "J4") (pin "MP4") (pinfunction "MP4_MP4") (pintype "bidirectional"))
      (node (ref "R13") (pin "1") (pinfunction "1_1") (pintype "passive"))
      (node (ref "R1_PWRUSB") (pin "1") (pinfunction "1_1") (pintype "passive"))
      (node (ref "R2-USB") (pin "2") (pinfunction "2_2") (pintype "passive"))
      (node (ref "R2-USB1") (pin "1") (pinfunction "1_1") (pintype "passive"))
      (node (ref "R2_BAT") (pin "1") (pinfunction "1_1") (pintype "passive"))
      (node (ref "R9") (pin "1") (pinfunction "1_1") (pintype "passive"))
      (node (ref "RESET_BUTTON") (pin "1") (pinfunction "1_1") (pintype "passive"))
      (node (ref "RESET_BUTTON") (pin "2") (pinfunction "2_2") (pintype "passive"))
      (node (ref "SENSOR2") (pin "1") (pinfunction "GND_1") (pintype "power_in"))
      (node (ref "SENSOR2") (pin "5") (pinfunction "SDO_5") (pintype "bidirectional"))
      (node (ref "SENSOR2") (pin "7") (pinfunction "GND_7") (pintype "power_in"))
      (node (ref "SJ1") (pin "1") (pinfunction "1_1") (pintype "passive"))
      (node (ref "TP4") (pin "TP") (pinfunction "TP_TP") (pintype "input"))
      (node (ref "TP5") (pin "TP") (pinfunction "TP_TP") (pintype "input"))
      (node (ref "U1") (pin "1") (pinfunction "GND_1") (pintype "power_in"))
      (node (ref "U1") (pin "28") (pinfunction "GND_28") (pintype "power_in"))
      (node (ref "U1") (pin "29_1") (pinfunction "GND_29_1") (pintype "power_in"))
      (node (ref "U1") (pin "29_2") (pinfunction "GND_29_2") (pintype "power_in"))
      (node (ref "U1") (pin "29_3") (pinfunction "GND_29_3") (pintype "power_in"))
      (node (ref "U1") (pin "29_4") (pinfunction "GND_29_4") (pintype "power_in"))
      (node (ref "U1") (pin "29_5") (pinfunction "GND_29_5") (pintype "power_in"))
      (node (ref "U1") (pin "29_6") (pinfunction "GND_29_6") (pintype "power_in"))
      (node (ref "U1") (pin "29_7") (pinfunction "GND_29_7") (pintype "power_in"))
      (node (ref "U1") (pin "29_8") (pinfunction "GND_29_8") (pintype "power_in"))
      (node (ref "U1") (pin "29_9") (pinfunction "GND_29_9") (pintype "power_in"))
      (node (ref "U2") (pin "1") (pinfunction "CTG_1") (pintype "power_in"))
      (node (ref "U2") (pin "4") (pinfunction "GND_4") (pintype "power_in"))
      (node (ref "U2") (pin "6") (pinfunction "QSTRT_6") (pintype "input"))
      (node (ref "U2") (pin "9") (pinfunction "EP_9") (pintype "power_in"))
      (node (ref "U3") (pin "4") (pinfunction "GND_4") (pintype "power_in"))
      (node (ref "U3") (pin "9") (pinfunction "EXP_9") (pintype "passive"))
      (node (ref "U4") (pin "2") (pinfunction "VSS_2") (pintype "power_in"))
      (node (ref "U5") (pin "13") (pinfunction "GND_13") (pintype "power_in"))
    )
    (net (code "14") (name "GPIO8") (class "Default")
      (node (ref "R1") (pin "1") (pinfunction "1_1") (pintype "passive"))
      (node (ref "U1") (pin "10") (pinfunction "IO8_10") (pintype "bidirectional"))
    )
    (net (code "15") (name "I2C_PW") (class "Default")
      (node (ref "C23") (pin "1") (pinfunction "1_1") (pintype "passive"))
      (node (ref "C24") (pin "1") (pinfunction "1_1") (pintype "passive"))
      (node (ref "R1_PINH") (pin "2") (pinfunction "2_2") (pintype "passive"))
      (node (ref "R2-PINH") (pin "2") (pinfunction "2_2") (pintype "passive"))
      (node (ref "SENSOR2") (pin "2") (pinfunction "CSB_2") (pintype "input"))
      (node (ref "SENSOR2") (pin "6") (pinfunction "VDDIO_6") (pintype "power_in"))
      (node (ref "SENSOR2") (pin "8") (pinfunction "VDD_8") (pintype "power_in"))
      (node (ref "U1") (pin "17") (pinfunction "IO19_17") (pintype "bidirectional"))
    )
    (net (code "16") (name "INT_RTC") (class "Default")
      (node (ref "R1_PINH1") (pin "1") (pinfunction "1_1") (pintype "passive"))
      (node (ref "TP15") (pin "TP") (pinfunction "TP_TP") (pintype "input"))
      (node (ref "U1") (pin "8") (pinfunction "IO0_8") (pintype "bidirectional"))
      (node (ref "U5") (pin "3") (pinfunction "SQW/~{INT}_3") (pintype "output"))
    )
    (net (code "17") (name "IO{slash}BOOT") (class "Default")
      (node (ref "BOOT_BUTTON") (pin "3") (pinfunction "3_3") (pintype "passive"))
      (node (ref "BOOT_BUTTON") (pin "4") (pinfunction "4_4") (pintype "passive"))
      (node (ref "C4") (pin "1") (pinfunction "1_1") (pintype "passive"))
      (node (ref "R_BOOT") (pin "1") (pinfunction "1_1") (pintype "passive"))
      (node (ref "U1") (pin "15") (pinfunction "IO9_15") (pintype "bidirectional"))
    )
    (net (code "18") (name "IO{slash}CHANGE") (class "Default")
      (node (ref "C5") (pin "1") (pinfunction "1_1") (pintype "passive"))
      (node (ref "CHANGE_BUTTON") (pin "3") (pinfunction "3_3") (pintype "passive"))
      (node (ref "CHANGE_BUTTON") (pin "4") (pinfunction "4_4") (pintype "passive"))
      (node (ref "R_CHANGE") (pin "1") (pinfunction "1_1") (pintype "passive"))
      (node (ref "U1") (pin "23") (pinfunction "IO15_23") (pintype "bidirectional"))
    )
    (net (code "19") (name "MISO") (class "Default")
      (node (ref "D1") (pin "2") (pinfunction "2_2") (pintype "passive"))
      (node (ref "J1") (pin "P7") (pinfunction "DAT0_P7") (pintype "bidirectional"))
      (node (ref "R7") (pin "1") (pinfunction "1_1") (pintype "passive"))
      (node (ref "TP6") (pin "TP") (pinfunction "TP_TP") (pintype "input"))
      (node (ref "U1") (pin "27") (pinfunction "IO2_27") (pintype "bidirectional"))
      (node (ref "U3") (pin "2") (pinfunction "DO(IO1)_2") (pintype "bidirectional"))
    )
    (net (code "20") (name "MOSI") (class "Default")
      (node (ref "D2") (pin "2") (pinfunction "2_2") (pintype "passive"))
      (node (ref "J1") (pin "P3") (pinfunction "CMD_P3") (pintype "bidirectional"))
      (node (ref "J3") (pin "14") (pinfunction "14_14") (pintype "bidirectional"))
      (node (ref "R6") (pin "1") (pinfunction "1_1") (pintype "passive"))
      (node (ref "TP7") (pin "TP") (pinfunction "TP_TP") (pintype "input"))
      (node (ref "U1") (pin "7") (pinfunction "IO7_7") (pintype "bidirectional"))
      (node (ref "U3") (pin "5") (pinfunction "DI(IO0)_5") (pintype "bidirectional"))
    )
    (net (code "21") (name "Net-(CHG_LED-PadC)") (class "Default")
      (node (ref "CHG_LED") (pin "C") (pinfunction "C_C") (pintype "passive"))
      (node (ref "R1_BAT") (pin "1") (pinfunction "1_1") (pintype "passive"))
    )
    (net (code "22") (name "Net-(D7-CATHODE)") (class "Default")
      (node (ref "C1_BAT1") (pin "1") (pinfunction "1_1") (pintype "passive"))
      (node (ref "D7") (pin "1") (pinfunction "CATHODE_1") (pintype "bidirectional"))
      (node (ref "IC2") (pin "1") (pinfunction "VIN_1") (pintype "bidirectional"))
      (node (ref "IC2") (pin "3") (pinfunction "CE_3") (pintype "bidirectional"))
      (node (ref "Q1") (pin "2") (pinfunction "S_2") (pintype "bidirectional"))
    )
    (net (code "23") (name "Net-(D8-CATHODE)") (class "Default")
      (node (ref "D8") (pin "1") (pinfunction "CATHODE_1") (pintype "bidirectional"))
      (node (ref "R_CAPACITOR") (pin "1") (pinfunction "1_1") (pintype "passive"))
    )
    (net (code "24") (name "Net-(D11-K)") (class "Default")
      (node (ref "C19") (pin "1") (pinfunction "1_1") (pintype "passive"))
      (node (ref "D11") (pin "1") (pinfunction "K_1") (pintype "bidirectional"))
      (node (ref "D9") (pin "2") (pinfunction "A_2") (pintype "bidirectional"))
    )
    (net (code "25") (name "Net-(EPD_C1-Pad2)") (class "Default")
      (node (ref "EPD_C1") (pin "2") (pinfunction "2_2") (pintype "passive"))
      (node (ref "J3") (pin "4") (pinfunction "4_4") (pintype "bidirectional"))
    )
    (net (code "26") (name "Net-(EPD_C2-Pad2)") (class "Default")
      (node (ref "EPD_C2") (pin "2") (pinfunction "2_2") (pintype "passive"))
      (node (ref "J3") (pin "5") (pinfunction "5_5") (pintype "bidirectional"))
    )
    (net (code "27") (name "Net-(EPD_C6-Pad2)") (class "Default")
      (node (ref "EPD_C6") (pin "2") (pinfunction "2_2") (pintype "passive"))
      (node (ref "J3") (pin "18") (pinfunction "18_18") (pintype "bidirectional"))
    )
    (net (code "28") (name "Net-(EPD_C7-Pad2)") (class "Default")
      (node (ref "EPD_C7") (pin "2") (pinfunction "2_2") (pintype "passive"))
      (node (ref "J3") (pin "19") (pinfunction "19_19") (pintype "bidirectional"))
    )
    (net (code "29") (name "Net-(EPD_C8-Pad2)") (class "Default")
      (node (ref "EPD_C8") (pin "2") (pinfunction "2_2") (pintype "passive"))
      (node (ref "J3") (pin "20") (pinfunction "20_20") (pintype "bidirectional"))
    )
    (net (code "30") (name "Net-(EPD_C10-Pad2)") (class "Default")
      (node (ref "EPD_C10") (pin "2") (pinfunction "2_2") (pintype "passive"))
      (node (ref "J3") (pin "22") (pinfunction "22_22") (pintype "bidirectional"))
    )
    (net (code "31") (name "Net-(EPD_C12-Pad2)") (class "Default")
      (node (ref "EPD_C12") (pin "2") (pinfunction "2_2") (pintype "passive"))
      (node (ref "J3") (pin "24") (pinfunction "24_24") (pintype "bidirectional"))
    )
    (net (code "32") (name "Net-(IC1-CT)") (class "Default")
      (node (ref "C_DELAY") (pin "1") (pinfunction "1_1") (pintype "passive"))
      (node (ref "IC1") (pin "5") (pinfunction "CT_5") (pintype "bidirectional"))
    )
    (net (code "33") (name "Net-(J4-PadA5)") (class "Default")
      (node (ref "J4") (pin "A5") (pinfunction "A5_A5") (pintype "bidirectional"))
      (node (ref "R2-USB1") (pin "2") (pinfunction "2_2") (pintype "passive"))
    )
    (net (code "34") (name "Net-(J4-PadB5)") (class "Default")
      (node (ref "J4") (pin "B5") (pinfunction "B5_B5") (pintype "bidirectional"))
      (node (ref "R2-USB") (pin "1") (pinfunction "1_1") (pintype "passive"))
    )
    (net (code "35") (name "Net-(U4-PROG)") (class "Default")
      (node (ref "R2_BAT") (pin "2") (pinfunction "2_2") (pintype "passive"))
      (node (ref "U4") (pin "5") (pinfunction "PROG_5") (pintype "input"))
    )
    (net (code "36") (name "Net-(U4-STAT)") (class "Default")
      (node (ref "R1_BAT") (pin "2") (pinfunction "2_2") (pintype "passive"))
      (node (ref "U4") (pin "1") (pinfunction "STAT_1") (pintype "output"))
    )
    (net (code "37") (name "PREVGH") (class "Default")
      (node (ref "D10") (pin "1") (pinfunction "K_1") (pintype "bidirectional"))
      (node (ref "EPD_C9") (pin "2") (pinfunction "2_2") (pintype "passive"))
      (node (ref "J3") (pin "21") (pinfunction "21_21") (pintype "bidirectional"))
    )
    (net (code "38") (name "PREVGL") (class "Default")
      (node (ref "D11") (pin "2") (pinfunction "A_2") (pintype "bidirectional"))
      (node (ref "EPD_C11") (pin "2") (pinfunction "2_2") (pintype "passive"))
      (node (ref "J3") (pin "23") (pinfunction "23_23") (pintype "bidirectional"))
    )
    (net (code "39") (name "RESE") (class "Default")
      (node (ref "J3") (pin "3") (pinfunction "3_3") (pintype "bidirectional"))
      (node (ref "Q3") (pin "2") (pinfunction "S_2") (pintype "bidirectional"))
      (node (ref "R12") (pin "2") (pinfunction "2_2") (pintype "passive"))
    )
    (net (code "40") (name "RESE'") (class "Default")
      (node (ref "R12") (pin "1") (pinfunction "1_1") (pintype "passive"))
      (node (ref "R9") (pin "2") (pinfunction "2_2") (pintype "passive"))
      (node (ref "SJ1") (pin "2") (pinfunction "2_2") (pintype "passive"))
    )
    (net (code "41") (name "RESET") (class "Default")
      (node (ref "C3") (pin "1") (pinfunction "1_1") (pintype "passive"))
      (node (ref "IC1") (pin "1") (pinfunction "VOUT_1") (pintype "bidirectional"))
      (node (ref "RESET_BUTTON") (pin "3") (pinfunction "3_3") (pintype "passive"))
      (node (ref "RESET_BUTTON") (pin "4") (pinfunction "4_4") (pintype "passive"))
      (node (ref "R_RESET") (pin "1") (pinfunction "1_1") (pintype "passive"))
      (node (ref "U1") (pin "3") (pinfunction "EN_3") (pintype "input"))
    )
    (net (code "42") (name "RTC_RST") (class "Default")
      (node (ref "U1") (pin "16") (pinfunction "IO18_16") (pintype "bidirectional"))
      (node (ref "U5") (pin "4") (pinfunction "~{RST}_4") (pintype "input"))
    )
    (net (code "43") (name "RX") (class "Default")
      (node (ref "TP2") (pin "TP") (pinfunction "TP_TP") (pintype "input"))
      (node (ref "U1") (pin "24") (pinfunction "RXD0/GPIO17_24") (pintype "bidirectional"))
    )
    (net (code "44") (name "SCK") (class "Default")
      (node (ref "D3") (pin "2") (pinfunction "2_2") (pintype "passive"))
      (node (ref "J1") (pin "P5") (pinfunction "CLK_P5") (pintype "bidirectional"))
      (node (ref "J3") (pin "13") (pinfunction "13_13") (pintype "bidirectional"))
      (node (ref "R5") (pin "1") (pinfunction "1_1") (pintype "passive"))
      (node (ref "TP8") (pin "TP") (pinfunction "TP_TP") (pintype "input"))
      (node (ref "U1") (pin "6") (pinfunction "IO6_6") (pintype "bidirectional"))
      (node (ref "U3") (pin "6") (pinfunction "CLK_6") (pintype "input"))
    )
    (net (code "45") (name "SCL") (class "Default")
      (node (ref "J2") (pin "4") (pinfunction "4_4") (pintype "passive"))
      (node (ref "R2-PINH") (pin "1") (pinfunction "1_1") (pintype "passive"))
      (node (ref "SENSOR2") (pin "4") (pinfunction "SCK_4") (pintype "input"))
      (node (ref "U1") (pin "20") (pinfunction "IO22_20") (pintype "bidirectional"))
      (node (ref "U2") (pin "7") (pinfunction "SCL_7") (pintype "input"))
      (node (ref "U5") (pin "16") (pinfunction "SCL_16") (pintype "input"))
    )
    (net (code "46") (name "SDA") (class "Default")
      (node (ref "J2") (pin "3") (pinfunction "3_3") (pintype "passive"))
      (node (ref "R1_PINH") (pin "1") (pinfunction "1_1") (pintype "passive"))
      (node (ref "SENSOR2") (pin "3") (pinfunction "SDI_3") (pintype "bidirectional"))
      (node (ref "U1") (pin "19") (pinfunction "IO21_19") (pintype "bidirectional"))
      (node (ref "U2") (pin "8") (pinfunction "SDA_8") (pintype "bidirectional"))
      (node (ref "U5") (pin "15") (pinfunction "SDA_15") (pintype "bidirectional"))
    )
    (net (code "47") (name "SRC") (class "Default")
      (node (ref "C19") (pin "2") (pinfunction "2_2") (pintype "passive"))
      (node (ref "D10") (pin "2") (pinfunction "A_2") (pintype "bidirectional"))
      (node (ref "L1") (pin "1") (pinfunction "1_1") (pintype "passive"))
      (node (ref "Q3") (pin "3") (pinfunction "D_3") (pintype "bidirectional"))
    )
    (net (code "48") (name "SS_SD") (class "Default")
      (node (ref "D6") (pin "2") (pinfunction "2_2") (pintype "passive"))
      (node (ref "J1") (pin "P2") (pinfunction "CD/DAT3_P2") (pintype "bidirectional"))
      (node (ref "R2") (pin "1") (pinfunction "1_1") (pintype "passive"))
      (node (ref "U1") (pin "4") (pinfunction "IO4_4") (pintype "bidirectional"))
    )
    (net (code "49") (name "TX") (class "Default")
      (node (ref "TP1") (pin "TP") (pinfunction "TP_TP") (pintype "input"))
      (node (ref "U1") (pin "25") (pinfunction "TXD0/GPIO16_25") (pintype "bidirectional"))
    )
    (net (code "50") (name "USB_D+") (class "Default")
      (node (ref "D12") (pin "1") (pinfunction "I/O1_1_1") (pintype "bidirectional"))
      (node (ref "U1") (pin "14") (pinfunction "IO13_14") (pintype "bidirectional"))
    )
    (net (code "51") (name "USB_D-") (class "Default")
      (node (ref "D12") (pin "3") (pinfunction "I/O2_1_3") (pintype "bidirectional"))
      (node (ref "U1") (pin "13") (pinfunction "IO12_13") (pintype "bidirectional"))
    )
    (net (code "52") (name "VBAT") (class "Default")
      (node (ref "C2_BAT") (pin "1") (pinfunction "1_1") (pintype "passive"))
      (node (ref "Q1") (pin "3") (pinfunction "D_3") (pintype "bidirectional"))
      (node (ref "TP3") (pin "TP") (pinfunction "TP_TP") (pintype "input"))
      (node (ref "U2") (pin "2") (pinfunction "CELL_2") (pintype "power_in"))
      (node (ref "U2") (pin "3") (pinfunction "VDD_3") (pintype "power_in"))
      (node (ref "U4") (pin "3") (pinfunction "VBAT_3") (pintype "power_in"))
    )
    (net (code "53") (name "VBUS") (class "Default")
      (node (ref "C1_BAT") (pin "1") (pinfunction "1_1") (pintype "passive"))
      (node (ref "C4_USB") (pin "1") (pinfunction "1_1") (pintype "passive"))
      (node (ref "C5_USB") (pin "1") (pinfunction "1_1") (pintype "passive"))
      (node (ref "CHG_LED") (pin "A") (pinfunction "A_A") (pintype "passive"))
      (node (ref "D12") (pin "5") (pinfunction "VBUS_5") (pintype "bidirectional"))
      (node (ref "D7") (pin "2") (pinfunction "ANODE_2") (pintype "bidirectional"))
      (node (ref "PFMF.050.1") (pin "2") (pinfunction "2_2") (pintype "passive"))
      (node (ref "Q1") (pin "1") (pinfunction "G_1") (pintype "bidirectional"))
      (node (ref "R1_PWRUSB") (pin "2") (pinfunction "2_2") (pintype "passive"))
      (node (ref "TP14") (pin "TP") (pinfunction "TP_TP") (pintype "input"))
      (node (ref "U4") (pin "4") (pinfunction "VIN_4") (pintype "power_in"))
    )
    (net (code "54") (name "VRTC") (class "Default")
      (node (ref "C10_SUPERCAP") (pin "1") (pinfunction "1_1") (pintype "passive"))
      (node (ref "C8") (pin "1") (pinfunction "1_1") (pintype "passive"))
      (node (ref "R_CAPACITOR") (pin "2") (pinfunction "2_2") (pintype "passive"))
      (node (ref "U5") (pin "14") (pinfunction "VBAT_14") (pintype "power_in"))
    )
    (net (code "55") (name "VUSB") (class "Default")
      (node (ref "J4") (pin "A4") (pinfunction "A4_A4") (pintype "bidirectional"))
      (node (ref "J4") (pin "A9") (pinfunction "A9_A9") (pintype "bidirectional"))
      (node (ref "J4") (pin "B4") (pinfunction "B4_B4") (pintype "bidirectional"))
      (node (ref "J4") (pin "B9") (pinfunction "B9_B9") (pintype "bidirectional"))
      (node (ref "PFMF.050.1") (pin "1") (pinfunction "1_1") (pintype "passive"))
    )
    (net (code "56") (name "unconnected-(IC1-NC-Pad4)") (class "Default")
      (node (ref "IC1") (pin "4") (pinfunction "NC_4") (pintype "no_connect"))
    )
    (net (code "57") (name "unconnected-(IC2-NC-Pad4)") (class "Default")
      (node (ref "IC2") (pin "4") (pinfunction "NC_4") (pintype "no_connect"))
    )
    (net (code "58") (name "unconnected-(J1-DAT1-PadP8)") (class "Default")
      (node (ref "J1") (pin "P8") (pinfunction "DAT1_P8") (pintype "bidirectional"))
    )
    (net (code "59") (name "unconnected-(J1-DAT2-PadP1)") (class "Default")
      (node (ref "J1") (pin "P1") (pinfunction "DAT2_P1") (pintype "bidirectional"))
    )
    (net (code "60") (name "unconnected-(J1-DETECTION_1-PadS1)") (class "Default")
      (node (ref "J1") (pin "S1") (pinfunction "DETECTION_1_S1") (pintype "bidirectional"))
    )
    (net (code "61") (name "unconnected-(J1-DETECTION_2-PadS2)") (class "Default")
      (node (ref "J1") (pin "S2") (pinfunction "DETECTION_2_S2") (pintype "bidirectional"))
    )
    (net (code "62") (name "unconnected-(J3-Pad1)") (class "Default")
      (node (ref "J3") (pin "1") (pinfunction "1_1") (pintype "bidirectional"))
    )
    (net (code "63") (name "unconnected-(J3-Pad6)") (class "Default")
      (node (ref "J3") (pin "6") (pinfunction "6_6") (pintype "bidirectional"))
    )
    (net (code "64") (name "unconnected-(J3-Pad7)") (class "Default")
      (node (ref "J3") (pin "7") (pinfunction "7_7") (pintype "bidirectional"))
    )
    (net (code "65") (name "unconnected-(J4-PadA8)") (class "Default")
      (node (ref "J4") (pin "A8") (pinfunction "A8_A8") (pintype "bidirectional"))
    )
    (net (code "66") (name "unconnected-(J4-PadB8)") (class "Default")
      (node (ref "J4") (pin "B8") (pinfunction "B8_B8") (pintype "bidirectional"))
    )
    (net (code "67") (name "unconnected-(U1-NC-Pad22)") (class "Default")
      (node (ref "U1") (pin "22") (pinfunction "NC_22") (pintype "no_connect"))
    )
    (net (code "68") (name "unconnected-(U2-~{ALERT}-Pad5)") (class "Default")
      (node (ref "U2") (pin "5") (pinfunction "~{ALERT}_5") (pintype "output"))
    )
  )
)
